# Placa_Control.net
KiCad netlist of a schematic drawn in Altium Designer
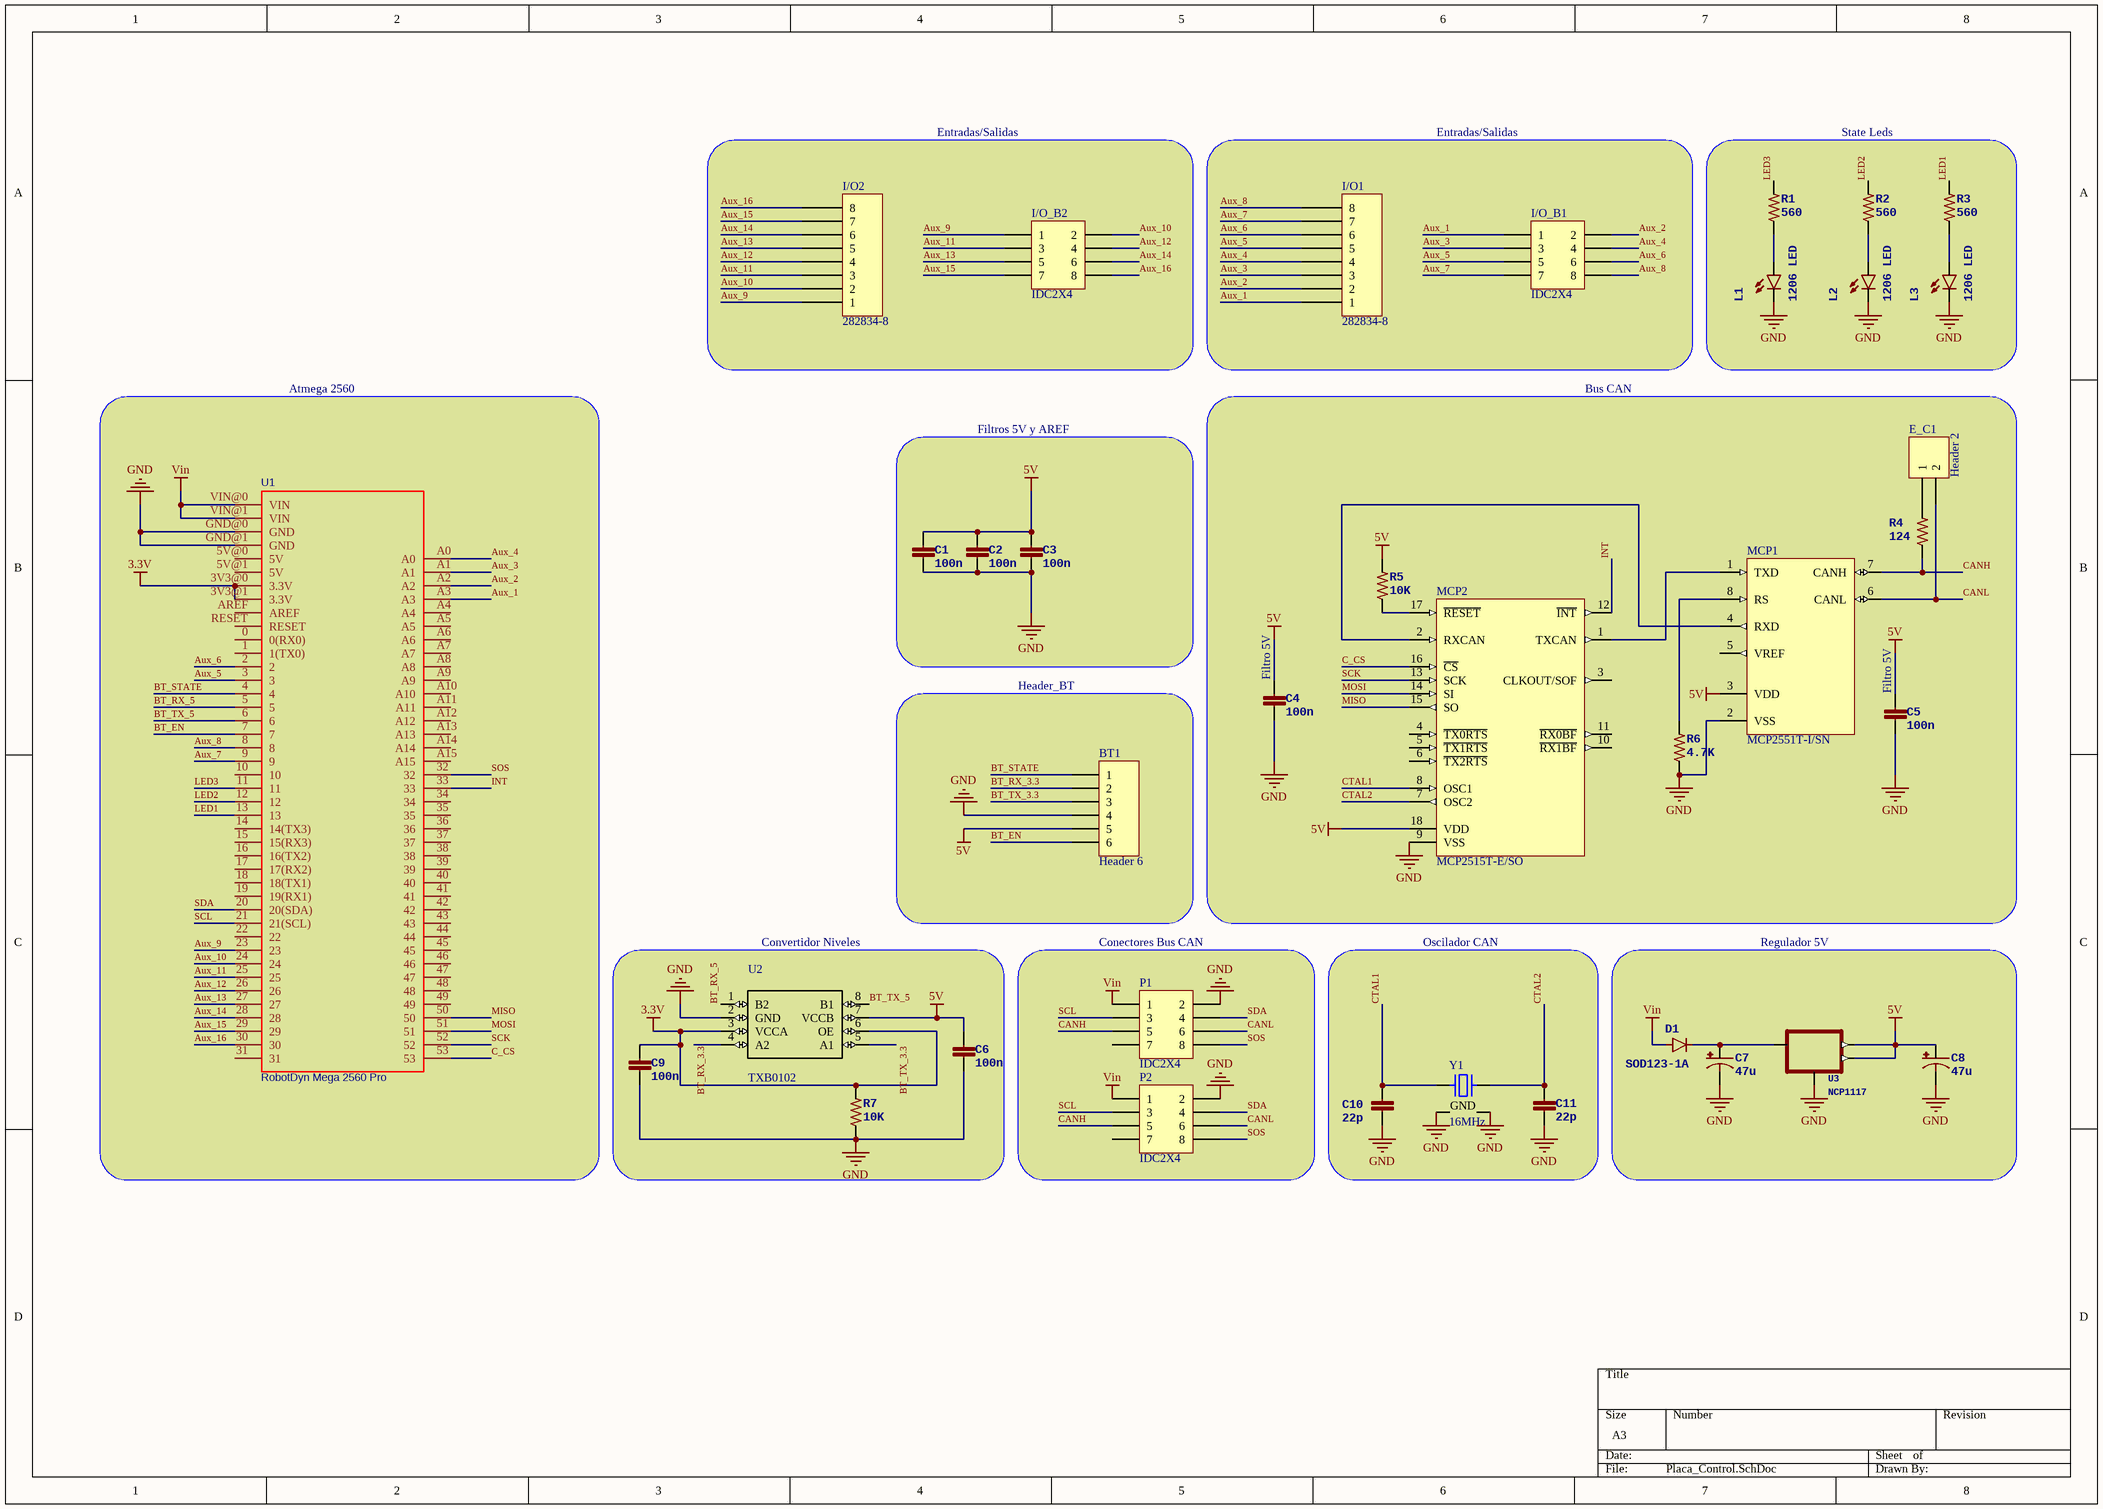
[diagram p0: Placa_Control.SchDoc]

(export (version "E")
  (design (tool "Eeschema 10.0.6"))
  (components
    (comp (ref "BT1")
      (value "Header 6")
      (footprint "HDR1X6")
      (description "Header, 6-Pin")
      (fields (field (name "PUBLISHER") "Altium Limited"))
      (libsource (lib "Miscellaneous Connectors") (part "Header 6"))
    )
    (comp (ref "C1")
      (value "100n")
      (footprint "SparkFun-Passives:0805")
      (libsource (lib "SparkFun-Passives") (part "CAP0805"))
    )
    (comp (ref "C2")
      (value "100n")
      (footprint "SparkFun-Passives:0805")
      (libsource (lib "SparkFun-Passives") (part "CAP0805"))
    )
    (comp (ref "C3")
      (value "100n")
      (footprint "SparkFun-Passives:0805")
      (libsource (lib "SparkFun-Passives") (part "CAP0805"))
    )
    (comp (ref "C4")
      (value "100n")
      (footprint "SparkFun-Passives:0805")
      (libsource (lib "SparkFun-Passives") (part "CAP0805"))
    )
    (comp (ref "C5")
      (value "100n")
      (footprint "SparkFun-Passives:0805")
      (libsource (lib "SparkFun-Passives") (part "CAP0805"))
    )
    (comp (ref "C6")
      (value "100n")
      (footprint "SparkFun-Passives:0805")
      (libsource (lib "SparkFun-Passives") (part "CAP0805"))
    )
    (comp (ref "C7")
      (value "47u")
      (footprint "PANASONIC_D")
      (libsource (lib "SparkFun-Capacitors") (part "47UF-50V-20%(ELECT)"))
    )
    (comp (ref "C8")
      (value "47u")
      (footprint "PANASONIC_D")
      (libsource (lib "SparkFun-Capacitors") (part "47UF-50V-20%(ELECT)"))
    )
    (comp (ref "C9")
      (value "100n")
      (footprint "SparkFun-Passives:0805")
      (libsource (lib "SparkFun-Passives") (part "CAP0805"))
    )
    (comp (ref "C10")
      (value "22p")
      (footprint "SparkFun-Passives:0805")
      (libsource (lib "SparkFun-Passives") (part "CAP0805"))
    )
    (comp (ref "C11")
      (value "22p")
      (footprint "SparkFun-Passives:0805")
      (libsource (lib "SparkFun-Passives") (part "CAP0805"))
    )
    (comp (ref "D1")
      (value "SOD123-1A")
      (footprint "SOD-123")
      (libsource (lib "SparkFun-DiscreteSemi") (part "DIODESOD123"))
    )
    (comp (ref "E_C1")
      (value "Header 2")
      (footprint "HDR1X2")
      (description "Header, 2-Pin")
      (fields (field (name "PUBLISHER") "Altium Limited"))
      (libsource (lib "Miscellaneous Connectors") (part "Header 2"))
    )
    (comp (ref "I/O1")
      (value "282834-8")
      (footprint "TE 282834-8")
      (description "TERM BLOCK 8POS SIDE ENT 2.54MM")
      (fields (field (name "MANUFACTURER") "TE Connectivity AMP Connectors") (field (name "VOLTAGE") "150V"))
      (libsource (lib "Connector - Terminal Block") (part "282834-8"))
    )
    (comp (ref "I/O2")
      (value "282834-8")
      (footprint "TE 282834-8")
      (description "TERM BLOCK 8POS SIDE ENT 2.54MM")
      (fields (field (name "MANUFACTURER") "TE Connectivity AMP Connectors") (field (name "VOLTAGE") "150V"))
      (libsource (lib "Connector - Terminal Block") (part "282834-8"))
    )
    (comp (ref "I/O_B1")
      (value "IDC2X4")
      (footprint "IDC:IDC2X4")
      (description "Header, 4-Pin, Dual row")
      (fields (field (name "PUBLISHER") "Altium Limited"))
      (libsource (lib "IDC") (part "IDC2X4"))
    )
    (comp (ref "I/O_B2")
      (value "IDC2X4")
      (footprint "IDC:IDC2X4")
      (description "Header, 4-Pin, Dual row")
      (fields (field (name "PUBLISHER") "Altium Limited"))
      (libsource (lib "IDC") (part "IDC2X4"))
    )
    (comp (ref "L1")
      (value "1206 LED")
      (footprint "SparkFun-LED:LED-1206")
      (libsource (lib "SparkFun-LED") (part "LED1206"))
    )
    (comp (ref "L2")
      (value "1206 LED")
      (footprint "SparkFun-LED:LED-1206")
      (libsource (lib "SparkFun-LED") (part "LED1206"))
    )
    (comp (ref "L3")
      (value "1206 LED")
      (footprint "SparkFun-LED:LED-1206")
      (libsource (lib "SparkFun-LED") (part "LED1206"))
    )
    (comp (ref "MCP1")
      (value "MCP2551T-I/SN")
      (footprint "SOIC-SN8_N")
      (description "High-Speed CAN Transceiver, 8-Pin SOIC, Industrial Temperature, Tape and Reel")
      (fields (field (name "PUBLISHER") "Altium Limited"))
      (libsource (lib "Microchip Interface") (part "MCP2551T-I/SN"))
    )
    (comp (ref "MCP2")
      (value "MCP2515T-E/SO")
      (footprint "SOIC-SO18_N")
      (description "Stand-Alone CAN Controller With SPI Interface, 18-Pin SOIC, Extended Temperature, Tape and Reel")
      (fields (field (name "PUBLISHER") "Altium Limited"))
      (libsource (lib "Microchip Interface") (part "MCP2515T-E/SO"))
    )
    (comp (ref "P1")
      (value "IDC2X4")
      (footprint "IDC:IDC2X4")
      (description "Header, 4-Pin, Dual row")
      (fields (field (name "PUBLISHER") "Altium Limited"))
      (libsource (lib "IDC") (part "IDC2X4"))
    )
    (comp (ref "P2")
      (value "IDC2X4")
      (footprint "IDC:IDC2X4")
      (description "Header, 4-Pin, Dual row")
      (fields (field (name "PUBLISHER") "Altium Limited"))
      (libsource (lib "IDC") (part "IDC2X4"))
    )
    (comp (ref "R1")
      (value "560")
      (footprint "SparkFun-Passives:0805")
      (libsource (lib "SparkFun-Passives") (part "RESISTOR0805-RES"))
    )
    (comp (ref "R2")
      (value "560")
      (footprint "SparkFun-Passives:0805")
      (libsource (lib "SparkFun-Passives") (part "RESISTOR0805-RES"))
    )
    (comp (ref "R3")
      (value "560")
      (footprint "SparkFun-Passives:0805")
      (libsource (lib "SparkFun-Passives") (part "RESISTOR0805-RES"))
    )
    (comp (ref "R4")
      (value "124")
      (footprint "SparkFun-Passives:0805")
      (libsource (lib "SparkFun-Passives") (part "RESISTOR0805-RES"))
    )
    (comp (ref "R5")
      (value "10K")
      (footprint "SparkFun-Passives:0805")
      (libsource (lib "SparkFun-Passives") (part "RESISTOR0805-RES"))
    )
    (comp (ref "R6")
      (value "4.7K")
      (footprint "SparkFun-Passives:0805")
      (libsource (lib "SparkFun-Passives") (part "RESISTOR0805-RES"))
    )
    (comp (ref "R7")
      (value "10K")
      (footprint "SparkFun-Passives:0805")
      (libsource (lib "SparkFun-Passives") (part "RESISTOR0805-RES"))
    )
    (comp (ref "U1")
      (value "RobotDyn Mega 2560 Pro")
      (footprint "Mega2560Pro_Layout")
      (fields (field (name "BOM_MANUFACTURER PART") "?"))
      (libsource (lib "Mega2560Pro") (part "RobotDyn Mega 2560 Pro"))
    )
    (comp (ref "U2")
      (value "TXB0102")
      (footprint "SOP50P310X90-8N")
      (description "2-Bit Bidirectional Voltage-Level Translator with Auto Direction Sensing and +/-15-kV ESD Protect")
      (fields (field (name "MF") "Texas Instruments"))
      (libsource (lib "TXB0102") (part "TXB0102"))
    )
    (comp (ref "U3")
      (value "NCP1117")
      (footprint "SparkFun-IC-Power:SOT223")
      (libsource (lib "SparkFun-IC-Power") (part "V_REG_LM1117SOT223"))
    )
    (comp (ref "Y1")
      (value "16MHz")
      (footprint "NDK NX3225SA")
      (description "CRYSTAL 16.0000MHZ 8PF SMD")
      (fields (field (name "PART NUMBER") "NX3225SA-16.000MHZ-STD-CSR-1") (field (name "MANUFACTURER") "NDK"))
      (libsource (lib "Oscillator - Crystal") (part "NDK Crystal NX3225SA"))
    )
  )
  (nets
    (net (code "1") (name "/Aux_1") (class "Default")
      (node (ref "I/O1") (pin "1") (pinfunction "1_1") (pintype "passive"))
      (node (ref "I/O_B1") (pin "1") (pinfunction "1_1") (pintype "passive"))
      (node (ref "U1") (pin "A3") (pinfunction "A3_A3") (pintype "passive"))
    )
    (net (code "2") (name "/Aux_2") (class "Default")
      (node (ref "I/O1") (pin "2") (pinfunction "2_2") (pintype "passive"))
      (node (ref "I/O_B1") (pin "2") (pinfunction "2_2") (pintype "passive"))
      (node (ref "U1") (pin "A2") (pinfunction "A2_A2") (pintype "passive"))
    )
    (net (code "3") (name "/Aux_3") (class "Default")
      (node (ref "I/O1") (pin "3") (pinfunction "3_3") (pintype "passive"))
      (node (ref "I/O_B1") (pin "3") (pinfunction "3_3") (pintype "passive"))
      (node (ref "U1") (pin "A1") (pinfunction "A1_A1") (pintype "passive"))
    )
    (net (code "4") (name "/Aux_4") (class "Default")
      (node (ref "I/O1") (pin "4") (pinfunction "4_4") (pintype "passive"))
      (node (ref "I/O_B1") (pin "4") (pinfunction "4_4") (pintype "passive"))
      (node (ref "U1") (pin "A0") (pinfunction "A0_A0") (pintype "passive"))
    )
    (net (code "5") (name "/Aux_5") (class "Default")
      (node (ref "I/O1") (pin "5") (pinfunction "5_5") (pintype "passive"))
      (node (ref "I/O_B1") (pin "5") (pinfunction "5_5") (pintype "passive"))
      (node (ref "U1") (pin "3") (pinfunction "3_3") (pintype "passive"))
    )
    (net (code "6") (name "/Aux_6") (class "Default")
      (node (ref "I/O1") (pin "6") (pinfunction "6_6") (pintype "passive"))
      (node (ref "I/O_B1") (pin "6") (pinfunction "6_6") (pintype "passive"))
      (node (ref "U1") (pin "2") (pinfunction "2_2") (pintype "passive"))
    )
    (net (code "7") (name "/Aux_7") (class "Default")
      (node (ref "I/O1") (pin "7") (pinfunction "7_7") (pintype "passive"))
      (node (ref "I/O_B1") (pin "7") (pinfunction "7_7") (pintype "passive"))
      (node (ref "U1") (pin "9") (pinfunction "9_9") (pintype "passive"))
    )
    (net (code "8") (name "/Aux_8") (class "Default")
      (node (ref "I/O1") (pin "8") (pinfunction "8_8") (pintype "passive"))
      (node (ref "I/O_B1") (pin "8") (pinfunction "8_8") (pintype "passive"))
      (node (ref "U1") (pin "8") (pinfunction "8_8") (pintype "passive"))
    )
    (net (code "9") (name "/Aux_9") (class "Default")
      (node (ref "I/O2") (pin "1") (pinfunction "1_1") (pintype "passive"))
      (node (ref "I/O_B2") (pin "1") (pinfunction "1_1") (pintype "passive"))
      (node (ref "U1") (pin "23") (pinfunction "23_23") (pintype "passive"))
    )
    (net (code "10") (name "/Aux_10") (class "Default")
      (node (ref "I/O2") (pin "2") (pinfunction "2_2") (pintype "passive"))
      (node (ref "I/O_B2") (pin "2") (pinfunction "2_2") (pintype "passive"))
      (node (ref "U1") (pin "24") (pinfunction "24_24") (pintype "passive"))
    )
    (net (code "11") (name "/Aux_11") (class "Default")
      (node (ref "I/O2") (pin "3") (pinfunction "3_3") (pintype "passive"))
      (node (ref "I/O_B2") (pin "3") (pinfunction "3_3") (pintype "passive"))
      (node (ref "U1") (pin "25") (pinfunction "25_25") (pintype "passive"))
    )
    (net (code "12") (name "/Aux_12") (class "Default")
      (node (ref "I/O2") (pin "4") (pinfunction "4_4") (pintype "passive"))
      (node (ref "I/O_B2") (pin "4") (pinfunction "4_4") (pintype "passive"))
      (node (ref "U1") (pin "26") (pinfunction "26_26") (pintype "passive"))
    )
    (net (code "13") (name "/Aux_13") (class "Default")
      (node (ref "I/O2") (pin "5") (pinfunction "5_5") (pintype "passive"))
      (node (ref "I/O_B2") (pin "5") (pinfunction "5_5") (pintype "passive"))
      (node (ref "U1") (pin "27") (pinfunction "27_27") (pintype "passive"))
    )
    (net (code "14") (name "/Aux_14") (class "Default")
      (node (ref "I/O2") (pin "6") (pinfunction "6_6") (pintype "passive"))
      (node (ref "I/O_B2") (pin "6") (pinfunction "6_6") (pintype "passive"))
      (node (ref "U1") (pin "28") (pinfunction "28_28") (pintype "passive"))
    )
    (net (code "15") (name "/Aux_15") (class "Default")
      (node (ref "I/O2") (pin "7") (pinfunction "7_7") (pintype "passive"))
      (node (ref "I/O_B2") (pin "7") (pinfunction "7_7") (pintype "passive"))
      (node (ref "U1") (pin "29") (pinfunction "29_29") (pintype "passive"))
    )
    (net (code "16") (name "/Aux_16") (class "Default")
      (node (ref "I/O2") (pin "8") (pinfunction "8_8") (pintype "passive"))
      (node (ref "I/O_B2") (pin "8") (pinfunction "8_8") (pintype "passive"))
      (node (ref "U1") (pin "30") (pinfunction "30_30") (pintype "passive"))
    )
    (net (code "17") (name "/BT_EN") (class "Default")
      (node (ref "BT1") (pin "6") (pinfunction "6_6") (pintype "passive"))
      (node (ref "U1") (pin "7") (pinfunction "7_7") (pintype "passive"))
    )
    (net (code "18") (name "/BT_RX_3.3") (class "Default")
      (node (ref "BT1") (pin "2") (pinfunction "2_2") (pintype "passive"))
      (node (ref "U2") (pin "4") (pinfunction "A2_4") (pintype "bidirectional"))
    )
    (net (code "19") (name "/BT_RX_5") (class "Default")
      (node (ref "U1") (pin "5") (pinfunction "5_5") (pintype "passive"))
      (node (ref "U2") (pin "1") (pinfunction "B2_1") (pintype "bidirectional"))
    )
    (net (code "20") (name "/BT_STATE") (class "Default")
      (node (ref "BT1") (pin "1") (pinfunction "1_1") (pintype "passive"))
      (node (ref "U1") (pin "4") (pinfunction "4_4") (pintype "passive"))
    )
    (net (code "21") (name "/BT_TX_3.3") (class "Default")
      (node (ref "BT1") (pin "3") (pinfunction "3_3") (pintype "passive"))
      (node (ref "U2") (pin "5") (pinfunction "A1_5") (pintype "bidirectional"))
    )
    (net (code "22") (name "/BT_TX_5") (class "Default")
      (node (ref "U1") (pin "6") (pinfunction "6_6") (pintype "passive"))
      (node (ref "U2") (pin "8") (pinfunction "B1_8") (pintype "bidirectional"))
    )
    (net (code "23") (name "/CANH") (class "Default")
      (node (ref "MCP1") (pin "7") (pinfunction "CANH_7") (pintype "bidirectional"))
      (node (ref "P1") (pin "5") (pinfunction "5_5") (pintype "passive"))
      (node (ref "P2") (pin "5") (pinfunction "5_5") (pintype "passive"))
      (node (ref "R4") (pin "1") (pinfunction "1_1") (pintype "passive"))
    )
    (net (code "24") (name "/CANL") (class "Default")
      (node (ref "E_C1") (pin "2") (pinfunction "2_2") (pintype "passive"))
      (node (ref "MCP1") (pin "6") (pinfunction "CANL_6") (pintype "bidirectional"))
      (node (ref "P1") (pin "6") (pinfunction "6_6") (pintype "passive"))
      (node (ref "P2") (pin "6") (pinfunction "6_6") (pintype "passive"))
    )
    (net (code "25") (name "/CTAL1") (class "Default")
      (node (ref "C10") (pin "1") (pinfunction "1_1") (pintype "passive"))
      (node (ref "MCP2") (pin "8") (pinfunction "OSC1_8") (pintype "input"))
      (node (ref "Y1") (pin "1") (pinfunction "1_1") (pintype "passive"))
    )
    (net (code "26") (name "/CTAL2") (class "Default")
      (node (ref "C11") (pin "1") (pinfunction "1_1") (pintype "passive"))
      (node (ref "MCP2") (pin "7") (pinfunction "OSC2_7") (pintype "output"))
      (node (ref "Y1") (pin "3") (pinfunction "3_3") (pintype "passive"))
    )
    (net (code "27") (name "/C_CS") (class "Default")
      (node (ref "MCP2") (pin "16") (pinfunction "~{CS}_16") (pintype "input"))
      (node (ref "U1") (pin "53") (pinfunction "53_53") (pintype "passive"))
    )
    (net (code "28") (name "/INT") (class "Default")
      (node (ref "MCP2") (pin "12") (pinfunction "~{INT}_12") (pintype "output"))
      (node (ref "U1") (pin "33") (pinfunction "33_33") (pintype "passive"))
    )
    (net (code "29") (name "/LED1") (class "Default")
      (node (ref "R3") (pin "2") (pinfunction "2_2") (pintype "passive"))
      (node (ref "U1") (pin "13") (pinfunction "13_13") (pintype "passive"))
    )
    (net (code "30") (name "/LED2") (class "Default")
      (node (ref "R2") (pin "2") (pinfunction "2_2") (pintype "passive"))
      (node (ref "U1") (pin "12") (pinfunction "12_12") (pintype "passive"))
    )
    (net (code "31") (name "/LED3") (class "Default")
      (node (ref "R1") (pin "2") (pinfunction "2_2") (pintype "passive"))
      (node (ref "U1") (pin "11") (pinfunction "11_11") (pintype "passive"))
    )
    (net (code "32") (name "/MISO") (class "Default")
      (node (ref "MCP2") (pin "15") (pinfunction "SO_15") (pintype "output"))
      (node (ref "U1") (pin "50") (pinfunction "50_50") (pintype "passive"))
    )
    (net (code "33") (name "/MOSI") (class "Default")
      (node (ref "MCP2") (pin "14") (pinfunction "SI_14") (pintype "input"))
      (node (ref "U1") (pin "51") (pinfunction "51_51") (pintype "passive"))
    )
    (net (code "34") (name "/SCK") (class "Default")
      (node (ref "MCP2") (pin "13") (pinfunction "SCK_13") (pintype "input"))
      (node (ref "U1") (pin "52") (pinfunction "52_52") (pintype "passive"))
    )
    (net (code "35") (name "/SCL") (class "Default")
      (node (ref "P1") (pin "3") (pinfunction "3_3") (pintype "passive"))
      (node (ref "P2") (pin "3") (pinfunction "3_3") (pintype "passive"))
      (node (ref "U1") (pin "21") (pinfunction "21(SCL)_21") (pintype "passive"))
    )
    (net (code "36") (name "/SDA") (class "Default")
      (node (ref "P1") (pin "4") (pinfunction "4_4") (pintype "passive"))
      (node (ref "P2") (pin "4") (pinfunction "4_4") (pintype "passive"))
      (node (ref "U1") (pin "20") (pinfunction "20(SDA)_20") (pintype "passive"))
    )
    (net (code "37") (name "/SOS") (class "Default")
      (node (ref "P1") (pin "8") (pinfunction "8_8") (pintype "passive"))
      (node (ref "P2") (pin "8") (pinfunction "8_8") (pintype "passive"))
      (node (ref "U1") (pin "32") (pinfunction "32_32") (pintype "passive"))
    )
    (net (code "38") (name "3.3V") (class "Default")
      (node (ref "C9") (pin "1") (pinfunction "1_1") (pintype "passive"))
      (node (ref "R7") (pin "2") (pinfunction "2_2") (pintype "passive"))
      (node (ref "U1") (pin "3V3@0") (pinfunction "3.3V_3V3@0") (pintype "passive"))
      (node (ref "U1") (pin "3V3@1") (pinfunction "3.3V_3V3@1") (pintype "passive"))
      (node (ref "U2") (pin "3") (pinfunction "VCCA_3") (pintype "bidirectional"))
      (node (ref "U2") (pin "6") (pinfunction "OE_6") (pintype "bidirectional"))
    )
    (net (code "39") (name "5V") (class "Default")
      (node (ref "BT1") (pin "5") (pinfunction "5_5") (pintype "passive"))
      (node (ref "C1") (pin "1") (pinfunction "1_1") (pintype "passive"))
      (node (ref "C2") (pin "1") (pinfunction "1_1") (pintype "passive"))
      (node (ref "C3") (pin "1") (pinfunction "1_1") (pintype "passive"))
      (node (ref "C4") (pin "1") (pinfunction "1_1") (pintype "passive"))
      (node (ref "C5") (pin "1") (pinfunction "1_1") (pintype "passive"))
      (node (ref "C6") (pin "1") (pinfunction "1_1") (pintype "passive"))
      (node (ref "C8") (pin "+") (pinfunction "+_+") (pintype "passive"))
      (node (ref "MCP1") (pin "3") (pinfunction "VDD_3") (pintype "power_in"))
      (node (ref "MCP2") (pin "18") (pinfunction "VDD_18") (pintype "power_in"))
      (node (ref "R5") (pin "2") (pinfunction "2_2") (pintype "passive"))
      (node (ref "U2") (pin "7") (pinfunction "VCCB_7") (pintype "bidirectional"))
      (node (ref "U3") (pin "2") (pinfunction "OUT_2") (pintype "output"))
      (node (ref "U3") (pin "4") (pinfunction "OUT@1_4") (pintype "output"))
    )
    (net (code "40") (name "GND") (class "Default")
      (node (ref "BT1") (pin "4") (pinfunction "4_4") (pintype "passive"))
      (node (ref "C1") (pin "2") (pinfunction "2_2") (pintype "passive"))
      (node (ref "C10") (pin "2") (pinfunction "2_2") (pintype "passive"))
      (node (ref "C11") (pin "2") (pinfunction "2_2") (pintype "passive"))
      (node (ref "C2") (pin "2") (pinfunction "2_2") (pintype "passive"))
      (node (ref "C3") (pin "2") (pinfunction "2_2") (pintype "passive"))
      (node (ref "C4") (pin "2") (pinfunction "2_2") (pintype "passive"))
      (node (ref "C5") (pin "2") (pinfunction "2_2") (pintype "passive"))
      (node (ref "C6") (pin "2") (pinfunction "2_2") (pintype "passive"))
      (node (ref "C7") (pin "-") (pinfunction "-_-") (pintype "passive"))
      (node (ref "C8") (pin "-") (pinfunction "-_-") (pintype "passive"))
      (node (ref "C9") (pin "2") (pinfunction "2_2") (pintype "passive"))
      (node (ref "L1") (pin "C") (pinfunction "C_C") (pintype "passive"))
      (node (ref "L2") (pin "C") (pinfunction "C_C") (pintype "passive"))
      (node (ref "L3") (pin "C") (pinfunction "C_C") (pintype "passive"))
      (node (ref "MCP1") (pin "2") (pinfunction "VSS_2") (pintype "power_in"))
      (node (ref "MCP2") (pin "9") (pinfunction "VSS_9") (pintype "power_in"))
      (node (ref "P1") (pin "2") (pinfunction "2_2") (pintype "passive"))
      (node (ref "P2") (pin "2") (pinfunction "2_2") (pintype "passive"))
      (node (ref "R6") (pin "1") (pinfunction "1_1") (pintype "passive"))
      (node (ref "R7") (pin "1") (pinfunction "1_1") (pintype "passive"))
      (node (ref "U1") (pin "GND@0") (pinfunction "GND_GND@0") (pintype "passive"))
      (node (ref "U1") (pin "GND@1") (pinfunction "GND_GND@1") (pintype "passive"))
      (node (ref "U2") (pin "2") (pinfunction "GND_2") (pintype "bidirectional"))
      (node (ref "U3") (pin "1") (pinfunction "ADJ_1") (pintype "passive"))
      (node (ref "Y1") (pin "2") (pinfunction "GND_2") (pintype "passive"))
      (node (ref "Y1") (pin "4") (pinfunction "GND_4") (pintype "passive"))
    )
    (net (code "41") (name "Net-(E_C1-Pad1)") (class "Default")
      (node (ref "E_C1") (pin "1") (pinfunction "1_1") (pintype "passive"))
      (node (ref "R4") (pin "2") (pinfunction "2_2") (pintype "passive"))
    )
    (net (code "42") (name "Net-(L1-PadA)") (class "Default")
      (node (ref "L1") (pin "A") (pinfunction "A_A") (pintype "passive"))
      (node (ref "R1") (pin "1") (pinfunction "1_1") (pintype "passive"))
    )
    (net (code "43") (name "Net-(L2-PadA)") (class "Default")
      (node (ref "L2") (pin "A") (pinfunction "A_A") (pintype "passive"))
      (node (ref "R2") (pin "1") (pinfunction "1_1") (pintype "passive"))
    )
    (net (code "44") (name "Net-(L3-PadA)") (class "Default")
      (node (ref "L3") (pin "A") (pinfunction "A_A") (pintype "passive"))
      (node (ref "R3") (pin "1") (pinfunction "1_1") (pintype "passive"))
    )
    (net (code "45") (name "Net-(MCP1-RS)") (class "Default")
      (node (ref "MCP1") (pin "8") (pinfunction "RS_8") (pintype "input"))
      (node (ref "R6") (pin "2") (pinfunction "2_2") (pintype "passive"))
    )
    (net (code "46") (name "Net-(MCP1-RXD)") (class "Default")
      (node (ref "MCP1") (pin "4") (pinfunction "RXD_4") (pintype "output"))
      (node (ref "MCP2") (pin "2") (pinfunction "RXCAN_2") (pintype "input"))
    )
    (net (code "47") (name "Net-(MCP1-TXD)") (class "Default")
      (node (ref "MCP1") (pin "1") (pinfunction "TXD_1") (pintype "input"))
      (node (ref "MCP2") (pin "1") (pinfunction "TXCAN_1") (pintype "output"))
    )
    (net (code "48") (name "Net-(MCP2-~{RESET})") (class "Default")
      (node (ref "MCP2") (pin "17") (pinfunction "~{RESET}_17") (pintype "input"))
      (node (ref "R5") (pin "1") (pinfunction "1_1") (pintype "passive"))
    )
    (net (code "49") (name "Net-(U3-IN)") (class "Default")
      (node (ref "C7") (pin "+") (pinfunction "+_+") (pintype "passive"))
      (node (ref "D1") (pin "C") (pinfunction "C_C") (pintype "passive"))
      (node (ref "U3") (pin "3") (pinfunction "IN_3") (pintype "passive"))
    )
    (net (code "50") (name "Vin") (class "Default")
      (node (ref "D1") (pin "A") (pinfunction "A_A") (pintype "passive"))
      (node (ref "P1") (pin "1") (pinfunction "1_1") (pintype "passive"))
      (node (ref "P2") (pin "1") (pinfunction "1_1") (pintype "passive"))
      (node (ref "U1") (pin "VIN@0") (pinfunction "VIN_VIN@0") (pintype "passive"))
      (node (ref "U1") (pin "VIN@1") (pinfunction "VIN_VIN@1") (pintype "passive"))
    )
    (net (code "51") (name "unconnected-(MCP1-VREF-Pad5)") (class "Default")
      (node (ref "MCP1") (pin "5") (pinfunction "VREF_5") (pintype "output"))
    )
    (net (code "52") (name "unconnected-(MCP2-CLKOUT{slash}SOF-Pad3)") (class "Default")
      (node (ref "MCP2") (pin "3") (pinfunction "CLKOUT/SOF_3") (pintype "output"))
    )
    (net (code "53") (name "unconnected-(MCP2-~{RX0BF}-Pad11)") (class "Default")
      (node (ref "MCP2") (pin "11") (pinfunction "~{RX0BF}_11") (pintype "output"))
    )
    (net (code "54") (name "unconnected-(MCP2-~{RX1BF}-Pad10)") (class "Default")
      (node (ref "MCP2") (pin "10") (pinfunction "~{RX1BF}_10") (pintype "output"))
    )
    (net (code "55") (name "unconnected-(MCP2-~{TX0RTS}-Pad4)") (class "Default")
      (node (ref "MCP2") (pin "4") (pinfunction "~{TX0RTS}_4") (pintype "input"))
    )
    (net (code "56") (name "unconnected-(MCP2-~{TX1RTS}-Pad5)") (class "Default")
      (node (ref "MCP2") (pin "5") (pinfunction "~{TX1RTS}_5") (pintype "input"))
    )
    (net (code "57") (name "unconnected-(MCP2-~{TX2RTS}-Pad6)") (class "Default")
      (node (ref "MCP2") (pin "6") (pinfunction "~{TX2RTS}_6") (pintype "input"))
    )
    (net (code "58") (name "unconnected-(P1-Pad7)") (class "Default")
      (node (ref "P1") (pin "7") (pinfunction "7_7") (pintype "passive"))
    )
    (net (code "59") (name "unconnected-(P2-Pad7)") (class "Default")
      (node (ref "P2") (pin "7") (pinfunction "7_7") (pintype "passive"))
    )
    (net (code "60") (name "unconnected-(U1-0(RX0)-Pad0)") (class "Default")
      (node (ref "U1") (pin "0") (pinfunction "0(RX0)_0") (pintype "passive"))
    )
    (net (code "61") (name "unconnected-(U1-1(TX0)-Pad1)") (class "Default")
      (node (ref "U1") (pin "1") (pinfunction "1(TX0)_1") (pintype "passive"))
    )
    (net (code "62") (name "unconnected-(U1-5V-Pad5V@0)") (class "Default")
      (node (ref "U1") (pin "5V@0") (pinfunction "5V_5V@0") (pintype "passive"))
    )
    (net (code "63") (name "unconnected-(U1-5V-Pad5V@1)") (class "Default")
      (node (ref "U1") (pin "5V@1") (pinfunction "5V_5V@1") (pintype "passive"))
    )
    (net (code "64") (name "unconnected-(U1-14(TX3)-Pad14)") (class "Default")
      (node (ref "U1") (pin "14") (pinfunction "14(TX3)_14") (pintype "passive"))
    )
    (net (code "65") (name "unconnected-(U1-15(RX3)-Pad15)") (class "Default")
      (node (ref "U1") (pin "15") (pinfunction "15(RX3)_15") (pintype "passive"))
    )
    (net (code "66") (name "unconnected-(U1-16(TX2)-Pad16)") (class "Default")
      (node (ref "U1") (pin "16") (pinfunction "16(TX2)_16") (pintype "passive"))
    )
    (net (code "67") (name "unconnected-(U1-17(RX2)-Pad17)") (class "Default")
      (node (ref "U1") (pin "17") (pinfunction "17(RX2)_17") (pintype "passive"))
    )
    (net (code "68") (name "unconnected-(U1-18(TX1)-Pad18)") (class "Default")
      (node (ref "U1") (pin "18") (pinfunction "18(TX1)_18") (pintype "passive"))
    )
    (net (code "69") (name "unconnected-(U1-19(RX1)-Pad19)") (class "Default")
      (node (ref "U1") (pin "19") (pinfunction "19(RX1)_19") (pintype "passive"))
    )
    (net (code "70") (name "unconnected-(U1-Pad10)") (class "Default")
      (node (ref "U1") (pin "10") (pinfunction "10_10") (pintype "passive"))
    )
    (net (code "71") (name "unconnected-(U1-Pad22)") (class "Default")
      (node (ref "U1") (pin "22") (pinfunction "22_22") (pintype "passive"))
    )
    (net (code "72") (name "unconnected-(U1-Pad31)") (class "Default")
      (node (ref "U1") (pin "31") (pinfunction "31_31") (pintype "passive"))
    )
    (net (code "73") (name "unconnected-(U1-Pad34)") (class "Default")
      (node (ref "U1") (pin "34") (pinfunction "34_34") (pintype "passive"))
    )
    (net (code "74") (name "unconnected-(U1-Pad35)") (class "Default")
      (node (ref "U1") (pin "35") (pinfunction "35_35") (pintype "passive"))
    )
    (net (code "75") (name "unconnected-(U1-Pad36)") (class "Default")
      (node (ref "U1") (pin "36") (pinfunction "36_36") (pintype "passive"))
    )
    (net (code "76") (name "unconnected-(U1-Pad37)") (class "Default")
      (node (ref "U1") (pin "37") (pinfunction "37_37") (pintype "passive"))
    )
    (net (code "77") (name "unconnected-(U1-Pad38)") (class "Default")
      (node (ref "U1") (pin "38") (pinfunction "38_38") (pintype "passive"))
    )
    (net (code "78") (name "unconnected-(U1-Pad39)") (class "Default")
      (node (ref "U1") (pin "39") (pinfunction "39_39") (pintype "passive"))
    )
    (net (code "79") (name "unconnected-(U1-Pad40)") (class "Default")
      (node (ref "U1") (pin "40") (pinfunction "40_40") (pintype "passive"))
    )
    (net (code "80") (name "unconnected-(U1-Pad41)") (class "Default")
      (node (ref "U1") (pin "41") (pinfunction "41_41") (pintype "passive"))
    )
    (net (code "81") (name "unconnected-(U1-Pad42)") (class "Default")
      (node (ref "U1") (pin "42") (pinfunction "42_42") (pintype "passive"))
    )
    (net (code "82") (name "unconnected-(U1-Pad43)") (class "Default")
      (node (ref "U1") (pin "43") (pinfunction "43_43") (pintype "passive"))
    )
    (net (code "83") (name "unconnected-(U1-Pad44)") (class "Default")
      (node (ref "U1") (pin "44") (pinfunction "44_44") (pintype "passive"))
    )
    (net (code "84") (name "unconnected-(U1-Pad45)") (class "Default")
      (node (ref "U1") (pin "45") (pinfunction "45_45") (pintype "passive"))
    )
    (net (code "85") (name "unconnected-(U1-Pad46)") (class "Default")
      (node (ref "U1") (pin "46") (pinfunction "46_46") (pintype "passive"))
    )
    (net (code "86") (name "unconnected-(U1-Pad47)") (class "Default")
      (node (ref "U1") (pin "47") (pinfunction "47_47") (pintype "passive"))
    )
    (net (code "87") (name "unconnected-(U1-Pad48)") (class "Default")
      (node (ref "U1") (pin "48") (pinfunction "48_48") (pintype "passive"))
    )
    (net (code "88") (name "unconnected-(U1-Pad49)") (class "Default")
      (node (ref "U1") (pin "49") (pinfunction "49_49") (pintype "passive"))
    )
    (net (code "89") (name "unconnected-(U1-PadA4)") (class "Default")
      (node (ref "U1") (pin "A4") (pinfunction "A4_A4") (pintype "passive"))
    )
    (net (code "90") (name "unconnected-(U1-PadA5)") (class "Default")
      (node (ref "U1") (pin "A5") (pinfunction "A5_A5") (pintype "passive"))
    )
    (net (code "91") (name "unconnected-(U1-PadA6)") (class "Default")
      (node (ref "U1") (pin "A6") (pinfunction "A6_A6") (pintype "passive"))
    )
    (net (code "92") (name "unconnected-(U1-PadA7)") (class "Default")
      (node (ref "U1") (pin "A7") (pinfunction "A7_A7") (pintype "passive"))
    )
    (net (code "93") (name "unconnected-(U1-PadA8)") (class "Default")
      (node (ref "U1") (pin "A8") (pinfunction "A8_A8") (pintype "passive"))
    )
    (net (code "94") (name "unconnected-(U1-PadA9)") (class "Default")
      (node (ref "U1") (pin "A9") (pinfunction "A9_A9") (pintype "passive"))
    )
    (net (code "95") (name "unconnected-(U1-PadA10)") (class "Default")
      (node (ref "U1") (pin "A10") (pinfunction "A10_A10") (pintype "passive"))
    )
    (net (code "96") (name "unconnected-(U1-PadA11)") (class "Default")
      (node (ref "U1") (pin "A11") (pinfunction "A11_A11") (pintype "passive"))
    )
    (net (code "97") (name "unconnected-(U1-PadA12)") (class "Default")
      (node (ref "U1") (pin "A12") (pinfunction "A12_A12") (pintype "passive"))
    )
    (net (code "98") (name "unconnected-(U1-PadA13)") (class "Default")
      (node (ref "U1") (pin "A13") (pinfunction "A13_A13") (pintype "passive"))
    )
    (net (code "99") (name "unconnected-(U1-PadA14)") (class "Default")
      (node (ref "U1") (pin "A14") (pinfunction "A14_A14") (pintype "passive"))
    )
    (net (code "100") (name "unconnected-(U1-PadA15)") (class "Default")
      (node (ref "U1") (pin "A15") (pinfunction "A15_A15") (pintype "passive"))
    )
    (net (code "101") (name "unconnected-(U1-PadAREF)") (class "Default")
      (node (ref "U1") (pin "AREF") (pinfunction "AREF_AREF") (pintype "passive"))
    )
    (net (code "102") (name "unconnected-(U1-PadRESET)") (class "Default")
      (node (ref "U1") (pin "RESET") (pinfunction "RESET_RESET") (pintype "passive"))
    )
  )
)
